# shower.net
KiCad netlist of a schematic drawn in Altium Designer
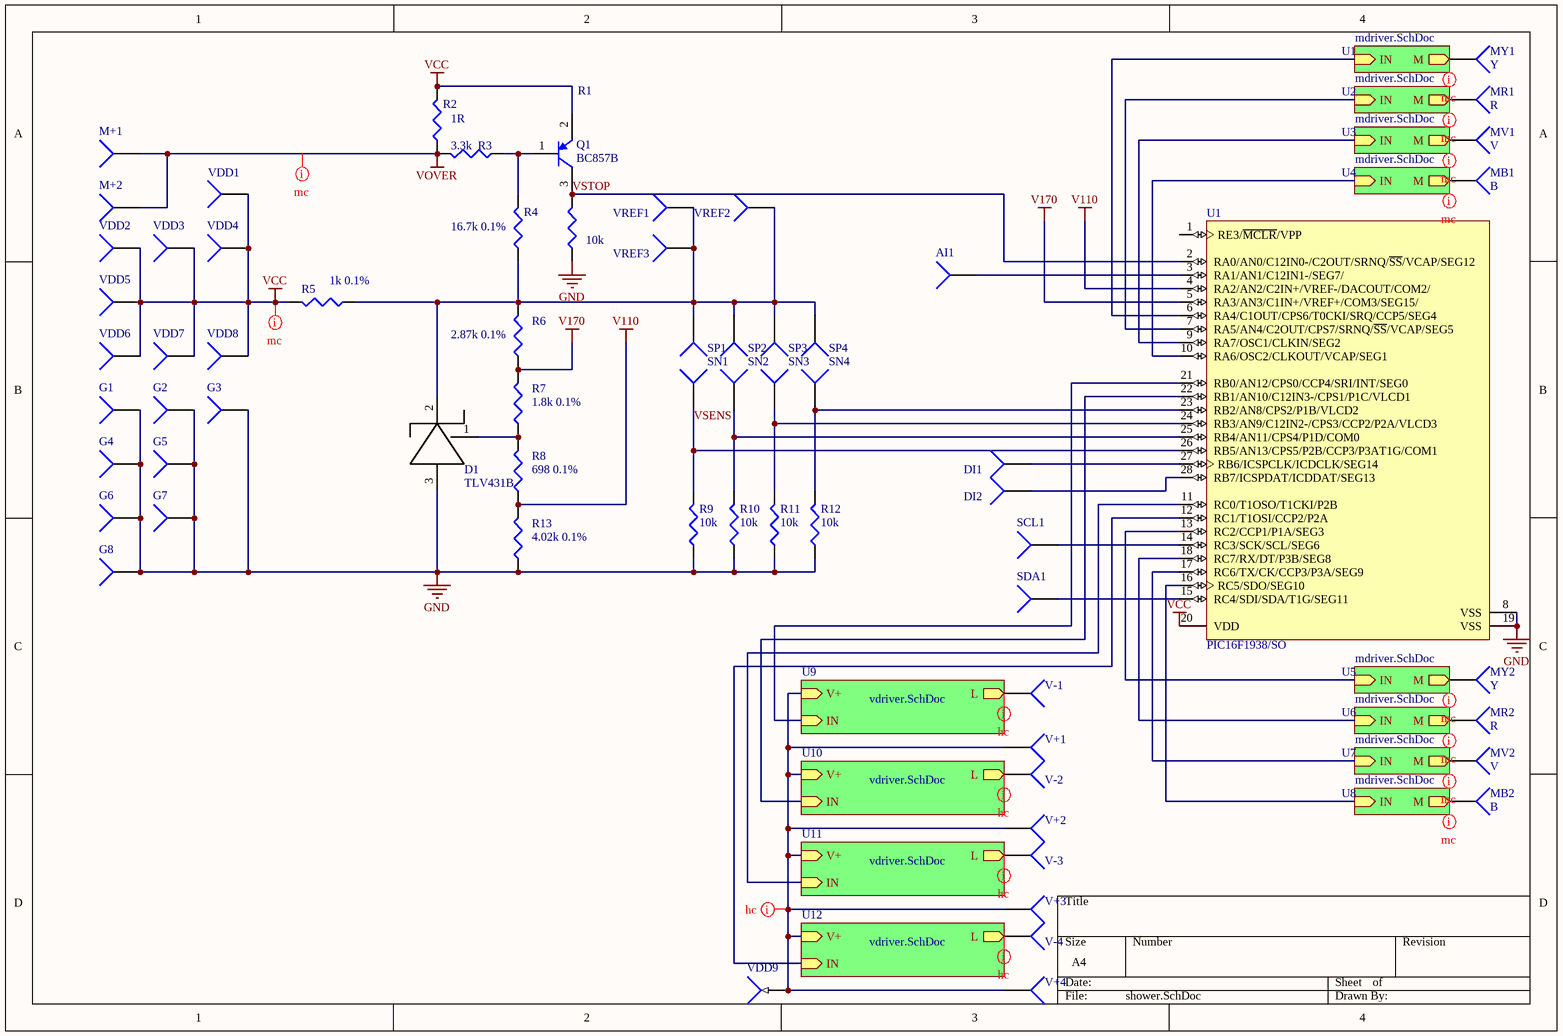
[diagram p0: shower.SchDoc]

(export (version "E")
  (design (tool "Eeschema 10.0.6"))
  (components
    (comp (ref "AI1")
      (value "+5V")
      (footprint "PIN1")
      (description "Socket")
      (fields (field (name "PUBLISHER") "Altium Limited"))
      (libsource (lib "misc") (part "Socket"))
    )
    (comp (ref "D1") (value "TLV431B") (footprint "SOT-23_N") (libsource (lib "misc") (part "TLV431A")))
    (comp (ref "DI1")
      (value "+5V")
      (footprint "PIN1")
      (description "Socket")
      (fields (field (name "PUBLISHER") "Altium Limited"))
      (libsource (lib "misc") (part "Socket"))
    )
    (comp (ref "DI2")
      (value "+5V")
      (footprint "PIN1")
      (description "Socket")
      (fields (field (name "PUBLISHER") "Altium Limited"))
      (libsource (lib "misc") (part "Socket"))
    )
    (comp (ref "G1")
      (value "Socket")
      (footprint "PIN1")
      (fields (field (name "PUBLISHER") "Altium Limited"))
      (libsource (lib "misc") (part "Socket"))
    )
    (comp (ref "G2")
      (value "Socket")
      (footprint "PIN1")
      (fields (field (name "PUBLISHER") "Altium Limited"))
      (libsource (lib "misc") (part "Socket"))
    )
    (comp (ref "G3")
      (value "Socket")
      (footprint "PIN1")
      (fields (field (name "PUBLISHER") "Altium Limited"))
      (libsource (lib "misc") (part "Socket"))
    )
    (comp (ref "G4")
      (value "Socket")
      (footprint "PIN1")
      (fields (field (name "PUBLISHER") "Altium Limited"))
      (libsource (lib "misc") (part "Socket"))
    )
    (comp (ref "G5")
      (value "Socket")
      (footprint "PIN1")
      (fields (field (name "PUBLISHER") "Altium Limited"))
      (libsource (lib "misc") (part "Socket"))
    )
    (comp (ref "G6")
      (value "Socket")
      (footprint "PIN1")
      (fields (field (name "PUBLISHER") "Altium Limited"))
      (libsource (lib "misc") (part "Socket"))
    )
    (comp (ref "G7")
      (value "Socket")
      (footprint "PIN1")
      (fields (field (name "PUBLISHER") "Altium Limited"))
      (libsource (lib "misc") (part "Socket"))
    )
    (comp (ref "G8")
      (value "Socket")
      (footprint "PIN1")
      (fields (field (name "PUBLISHER") "Altium Limited"))
      (libsource (lib "misc") (part "Socket"))
    )
    (comp (ref "M+1")
      (value "+5V")
      (footprint "PIN1")
      (description "Socket")
      (fields (field (name "PUBLISHER") "Altium Limited"))
      (libsource (lib "misc") (part "Socket"))
    )
    (comp (ref "M+2")
      (value "+5V")
      (footprint "PIN1")
      (description "Socket")
      (fields (field (name "PUBLISHER") "Altium Limited"))
      (libsource (lib "misc") (part "Socket"))
    )
    (comp (ref "MB1")
      (value "B")
      (footprint "PIN1")
      (description "Socket")
      (fields (field (name "PUBLISHER") "Altium Limited"))
      (libsource (lib "misc") (part "Socket"))
    )
    (comp (ref "MB2")
      (value "B")
      (footprint "PIN1")
      (description "Socket")
      (fields (field (name "PUBLISHER") "Altium Limited"))
      (libsource (lib "misc") (part "Socket"))
    )
    (comp (ref "MR1")
      (value "R")
      (footprint "PIN1")
      (description "Socket")
      (fields (field (name "PUBLISHER") "Altium Limited"))
      (libsource (lib "misc") (part "Socket"))
    )
    (comp (ref "MR2")
      (value "R")
      (footprint "PIN1")
      (description "Socket")
      (fields (field (name "PUBLISHER") "Altium Limited"))
      (libsource (lib "misc") (part "Socket"))
    )
    (comp (ref "MV1")
      (value "V")
      (footprint "PIN1")
      (description "Socket")
      (fields (field (name "PUBLISHER") "Altium Limited"))
      (libsource (lib "misc") (part "Socket"))
    )
    (comp (ref "MV2")
      (value "V")
      (footprint "PIN1")
      (description "Socket")
      (fields (field (name "PUBLISHER") "Altium Limited"))
      (libsource (lib "misc") (part "Socket"))
    )
    (comp (ref "MY1")
      (value "Y")
      (footprint "PIN1")
      (description "Socket")
      (fields (field (name "PUBLISHER") "Altium Limited"))
      (libsource (lib "misc") (part "Socket"))
    )
    (comp (ref "MY2")
      (value "Y")
      (footprint "PIN1")
      (description "Socket")
      (fields (field (name "PUBLISHER") "Altium Limited"))
      (libsource (lib "misc") (part "Socket"))
    )
    (comp (ref "Q1")
      (value "BC857B")
      (footprint "SOT-23_N")
      (description "PNP Bipolar Transistor")
      (fields (field (name "PUBLISHER") "Altium Limited"))
      (libsource (lib "Miscellaneous Devices") (part "PNP"))
    )
    (comp (ref "R1")
      (value "10k")
      (footprint "J1-0603")
      (description "Resistor")
      (fields (field (name "PUBLISHER") "Altium Limited"))
      (libsource (lib "Miscellaneous Devices") (part "Res3"))
    )
    (comp (ref "R2")
      (value "1R")
      (footprint "J1-0603")
      (description "Resistor")
      (fields (field (name "PUBLISHER") "Altium Limited"))
      (libsource (lib "Miscellaneous Devices") (part "Res3"))
    )
    (comp (ref "R3")
      (value "3.3k")
      (footprint "J1-0603")
      (description "Resistor")
      (fields (field (name "PUBLISHER") "Altium Limited"))
      (libsource (lib "Miscellaneous Devices") (part "Res3"))
    )
    (comp (ref "R4")
      (value "16.7k 0.1%")
      (footprint "J1-0603")
      (description "Resistor")
      (fields (field (name "PUBLISHER") "Altium Limited"))
      (libsource (lib "Miscellaneous Devices") (part "Res3"))
    )
    (comp (ref "R5")
      (value "1k 0.1%")
      (footprint "J1-0603")
      (description "Resistor")
      (fields (field (name "PUBLISHER") "Altium Limited"))
      (libsource (lib "Miscellaneous Devices") (part "Res3"))
    )
    (comp (ref "R6")
      (value "2.87k 0.1%")
      (footprint "J1-0603")
      (description "Resistor")
      (fields (field (name "PUBLISHER") "Altium Limited"))
      (libsource (lib "Miscellaneous Devices") (part "Res3"))
    )
    (comp (ref "R7")
      (value "1.8k 0.1%")
      (footprint "J1-0603")
      (description "Resistor")
      (fields (field (name "PUBLISHER") "Altium Limited"))
      (libsource (lib "Miscellaneous Devices") (part "Res3"))
    )
    (comp (ref "R8")
      (value "698 0.1%")
      (footprint "J1-0603")
      (description "Resistor")
      (fields (field (name "PUBLISHER") "Altium Limited"))
      (libsource (lib "Miscellaneous Devices") (part "Res3"))
    )
    (comp (ref "R9")
      (value "10k")
      (footprint "J1-0603")
      (description "Resistor")
      (fields (field (name "PUBLISHER") "Altium Limited"))
      (libsource (lib "Miscellaneous Devices") (part "Res3"))
    )
    (comp (ref "R10")
      (value "10k")
      (footprint "J1-0603")
      (description "Resistor")
      (fields (field (name "PUBLISHER") "Altium Limited"))
      (libsource (lib "Miscellaneous Devices") (part "Res3"))
    )
    (comp (ref "R11")
      (value "10k")
      (footprint "J1-0603")
      (description "Resistor")
      (fields (field (name "PUBLISHER") "Altium Limited"))
      (libsource (lib "Miscellaneous Devices") (part "Res3"))
    )
    (comp (ref "R12")
      (value "10k")
      (footprint "J1-0603")
      (description "Resistor")
      (fields (field (name "PUBLISHER") "Altium Limited"))
      (libsource (lib "Miscellaneous Devices") (part "Res3"))
    )
    (comp (ref "R13")
      (value "4.02k 0.1%")
      (footprint "J1-0603")
      (description "Resistor")
      (fields (field (name "PUBLISHER") "Altium Limited"))
      (libsource (lib "Miscellaneous Devices") (part "Res3"))
    )
    (comp (ref "SCL1")
      (value "+5V")
      (footprint "PIN1")
      (description "Socket")
      (fields (field (name "PUBLISHER") "Altium Limited"))
      (libsource (lib "misc") (part "Socket"))
    )
    (comp (ref "SDA1")
      (value "+5V")
      (footprint "PIN1")
      (description "Socket")
      (fields (field (name "PUBLISHER") "Altium Limited"))
      (libsource (lib "misc") (part "Socket"))
    )
    (comp (ref "SN1")
      (value "+5V")
      (footprint "PIN1")
      (description "Socket")
      (fields (field (name "PUBLISHER") "Altium Limited"))
      (libsource (lib "misc") (part "Socket"))
    )
    (comp (ref "SN2")
      (value "+5V")
      (footprint "PIN1")
      (description "Socket")
      (fields (field (name "PUBLISHER") "Altium Limited"))
      (libsource (lib "misc") (part "Socket"))
    )
    (comp (ref "SN3")
      (value "+5V")
      (footprint "PIN1")
      (description "Socket")
      (fields (field (name "PUBLISHER") "Altium Limited"))
      (libsource (lib "misc") (part "Socket"))
    )
    (comp (ref "SN4")
      (value "+5V")
      (footprint "PIN1")
      (description "Socket")
      (fields (field (name "PUBLISHER") "Altium Limited"))
      (libsource (lib "misc") (part "Socket"))
    )
    (comp (ref "SP1")
      (value "+5V")
      (footprint "PIN1")
      (description "Socket")
      (fields (field (name "PUBLISHER") "Altium Limited"))
      (libsource (lib "misc") (part "Socket"))
    )
    (comp (ref "SP2")
      (value "+5V")
      (footprint "PIN1")
      (description "Socket")
      (fields (field (name "PUBLISHER") "Altium Limited"))
      (libsource (lib "misc") (part "Socket"))
    )
    (comp (ref "SP3")
      (value "+5V")
      (footprint "PIN1")
      (description "Socket")
      (fields (field (name "PUBLISHER") "Altium Limited"))
      (libsource (lib "misc") (part "Socket"))
    )
    (comp (ref "SP4")
      (value "+5V")
      (footprint "PIN1")
      (description "Socket")
      (fields (field (name "PUBLISHER") "Altium Limited"))
      (libsource (lib "misc") (part "Socket"))
    )
    (comp (ref "U1")
      (value "PIC16F1938/SO")
      (footprint "SOIC-SO28_N")
      (fields (field (name "PUBLISHER") "Altium Limited"))
      (libsource (lib "Microchip Microcontroller 8-Bit PIC16") (part "PIC16F1936T-I/SO"))
    )
    (comp (ref "V+1")
      (value "+5V")
      (footprint "PIN1")
      (description "Socket")
      (fields (field (name "PUBLISHER") "Altium Limited"))
      (libsource (lib "misc") (part "Socket"))
    )
    (comp (ref "V+2")
      (value "+5V")
      (footprint "PIN1")
      (description "Socket")
      (fields (field (name "PUBLISHER") "Altium Limited"))
      (libsource (lib "misc") (part "Socket"))
    )
    (comp (ref "V+3")
      (value "+5V")
      (footprint "PIN1")
      (description "Socket")
      (fields (field (name "PUBLISHER") "Altium Limited"))
      (libsource (lib "misc") (part "Socket"))
    )
    (comp (ref "V+4")
      (value "+5V")
      (footprint "PIN1")
      (description "Socket")
      (fields (field (name "PUBLISHER") "Altium Limited"))
      (libsource (lib "misc") (part "Socket"))
    )
    (comp (ref "V-1")
      (value "+5V")
      (footprint "PIN1")
      (description "Socket")
      (fields (field (name "PUBLISHER") "Altium Limited"))
      (libsource (lib "misc") (part "Socket"))
    )
    (comp (ref "V-2")
      (value "+5V")
      (footprint "PIN1")
      (description "Socket")
      (fields (field (name "PUBLISHER") "Altium Limited"))
      (libsource (lib "misc") (part "Socket"))
    )
    (comp (ref "V-3")
      (value "+5V")
      (footprint "PIN1")
      (description "Socket")
      (fields (field (name "PUBLISHER") "Altium Limited"))
      (libsource (lib "misc") (part "Socket"))
    )
    (comp (ref "V-4")
      (value "+5V")
      (footprint "PIN1")
      (description "Socket")
      (fields (field (name "PUBLISHER") "Altium Limited"))
      (libsource (lib "misc") (part "Socket"))
    )
    (comp (ref "VDD1")
      (value "+5V")
      (footprint "PIN1")
      (description "Socket")
      (fields (field (name "PUBLISHER") "Altium Limited"))
      (libsource (lib "misc") (part "Socket"))
    )
    (comp (ref "VDD2")
      (value "+5V")
      (footprint "PIN1")
      (description "Socket")
      (fields (field (name "PUBLISHER") "Altium Limited"))
      (libsource (lib "misc") (part "Socket"))
    )
    (comp (ref "VDD3")
      (value "+5V")
      (footprint "PIN1")
      (description "Socket")
      (fields (field (name "PUBLISHER") "Altium Limited"))
      (libsource (lib "misc") (part "Socket"))
    )
    (comp (ref "VDD4")
      (value "+5V")
      (footprint "PIN1")
      (description "Socket")
      (fields (field (name "PUBLISHER") "Altium Limited"))
      (libsource (lib "misc") (part "Socket"))
    )
    (comp (ref "VDD5")
      (value "+5V")
      (footprint "PIN1")
      (description "Socket")
      (fields (field (name "PUBLISHER") "Altium Limited"))
      (libsource (lib "misc") (part "Socket"))
    )
    (comp (ref "VDD6")
      (value "+5V")
      (footprint "PIN1")
      (description "Socket")
      (fields (field (name "PUBLISHER") "Altium Limited"))
      (libsource (lib "misc") (part "Socket"))
    )
    (comp (ref "VDD7")
      (value "+5V")
      (footprint "PIN1")
      (description "Socket")
      (fields (field (name "PUBLISHER") "Altium Limited"))
      (libsource (lib "misc") (part "Socket"))
    )
    (comp (ref "VDD8")
      (value "+5V")
      (footprint "PIN1")
      (description "Socket")
      (fields (field (name "PUBLISHER") "Altium Limited"))
      (libsource (lib "misc") (part "Socket"))
    )
    (comp (ref "VDD9")
      (value "+5V")
      (footprint "PIN1")
      (description "Socket")
      (fields (field (name "PUBLISHER") "Altium Limited"))
      (libsource (lib "misc") (part "Socket"))
    )
    (comp (ref "VREF1")
      (value "+5V")
      (footprint "PIN1")
      (description "Socket")
      (fields (field (name "PUBLISHER") "Altium Limited"))
      (libsource (lib "misc") (part "Socket"))
    )
    (comp (ref "VREF2")
      (value "+5V")
      (footprint "PIN1")
      (description "Socket")
      (fields (field (name "PUBLISHER") "Altium Limited"))
      (libsource (lib "misc") (part "Socket"))
    )
    (comp (ref "VREF3")
      (value "+5V")
      (footprint "PIN1")
      (description "Socket")
      (fields (field (name "PUBLISHER") "Altium Limited"))
      (libsource (lib "misc") (part "Socket"))
    )
  )
  (nets
    (net (code "1") (name "/IN") (class "Default")
      (node (ref "U1") (pin "18") (pinfunction "RC7/RX/DT/P3B/SEG8_18") (pintype "bidirectional"))
    )
    (net (code "2") (name "/IN_1") (class "Default")
      (node (ref "U1") (pin "12") (pinfunction "RC1/T1OSI/CCP2/P2A_12") (pintype "bidirectional"))
    )
    (net (code "3") (name "/IN_2") (class "Default")
      (node (ref "U1") (pin "11") (pinfunction "RC0/T1OSO/T1CKI/P2B_11") (pintype "bidirectional"))
    )
    (net (code "4") (name "/IN_3") (class "Default")
      (node (ref "U1") (pin "22") (pinfunction "RB1/AN10/C12IN3-/CPS1/P1C/VLCD1_22") (pintype "bidirectional"))
    )
    (net (code "5") (name "/IN_4") (class "Default")
      (node (ref "U1") (pin "21") (pinfunction "RB0/AN12/CPS0/CCP4/SRI/INT/SEG0_21") (pintype "bidirectional"))
    )
    (net (code "6") (name "/IN_5") (class "Default")
      (node (ref "U1") (pin "13") (pinfunction "RC2/CCP1/P1A/SEG3_13") (pintype "bidirectional"))
    )
    (net (code "7") (name "/IN_6") (class "Default")
      (node (ref "U1") (pin "17") (pinfunction "RC6/TX/CK/CCP3/P3A/SEG9_17") (pintype "bidirectional"))
    )
    (net (code "8") (name "/IN_7") (class "Default")
      (node (ref "U1") (pin "16") (pinfunction "RC5/SDO/SEG10_16") (pintype "bidirectional"))
    )
    (net (code "9") (name "/IN_8") (class "Default")
      (node (ref "U1") (pin "6") (pinfunction "RA4/C1OUT/CPS6/T0CKI/SRQ/CCP5/SEG4_6") (pintype "bidirectional"))
    )
    (net (code "10") (name "/IN_9") (class "Default")
      (node (ref "U1") (pin "7") (pinfunction "RA5/AN4/C2OUT/CPS7/SRNQ/~{SS}/VCAP/SEG5_7") (pintype "bidirectional"))
    )
    (net (code "11") (name "/IN_10") (class "Default")
      (node (ref "U1") (pin "9") (pinfunction "RA7/OSC1/CLKIN/SEG2_9") (pintype "bidirectional"))
    )
    (net (code "12") (name "/IN_11") (class "Default")
      (node (ref "U1") (pin "10") (pinfunction "RA6/OSC2/CLKOUT/VCAP/SEG1_10") (pintype "bidirectional"))
    )
    (net (code "13") (name "/L") (class "Default")
      (node (ref "V-4") (pin "1") (pinfunction "1_1") (pintype "passive"))
    )
    (net (code "14") (name "/L_1") (class "Default")
      (node (ref "V-3") (pin "1") (pinfunction "1_1") (pintype "passive"))
    )
    (net (code "15") (name "/L_2") (class "Default")
      (node (ref "V-1") (pin "1") (pinfunction "1_1") (pintype "passive"))
    )
    (net (code "16") (name "/L_3") (class "Default")
      (node (ref "V-2") (pin "1") (pinfunction "1_1") (pintype "passive"))
    )
    (net (code "17") (name "/M") (class "Default")
      (node (ref "MB2") (pin "1") (pinfunction "1_1") (pintype "passive"))
    )
    (net (code "18") (name "/M_1") (class "Default")
      (node (ref "MB1") (pin "1") (pinfunction "1_1") (pintype "passive"))
    )
    (net (code "19") (name "/M_2") (class "Default")
      (node (ref "MR1") (pin "1") (pinfunction "1_1") (pintype "passive"))
    )
    (net (code "20") (name "/M_3") (class "Default")
      (node (ref "MV1") (pin "1") (pinfunction "1_1") (pintype "passive"))
    )
    (net (code "21") (name "/M_4") (class "Default")
      (node (ref "MY1") (pin "1") (pinfunction "1_1") (pintype "passive"))
    )
    (net (code "22") (name "/M_5") (class "Default")
      (node (ref "MY2") (pin "1") (pinfunction "1_1") (pintype "passive"))
    )
    (net (code "23") (name "/M_6") (class "Default")
      (node (ref "MR2") (pin "1") (pinfunction "1_1") (pintype "passive"))
    )
    (net (code "24") (name "/M_7") (class "Default")
      (node (ref "MV2") (pin "1") (pinfunction "1_1") (pintype "passive"))
    )
    (net (code "25") (name "/V+") (class "Default")
      (node (ref "V+1") (pin "1") (pinfunction "1_1") (pintype "passive"))
      (node (ref "V+2") (pin "1") (pinfunction "1_1") (pintype "passive"))
      (node (ref "V+3") (pin "1") (pinfunction "1_1") (pintype "passive"))
      (node (ref "V+4") (pin "1") (pinfunction "1_1") (pintype "passive"))
      (node (ref "VDD9") (pin "1") (pinfunction "1_1") (pintype "passive"))
    )
    (net (code "26") (name "/VSENS") (class "Default")
      (node (ref "R9") (pin "2") (pinfunction "2_2") (pintype "passive"))
      (node (ref "SN1") (pin "1") (pinfunction "1_1") (pintype "passive"))
      (node (ref "U1") (pin "26") (pinfunction "RB5/AN13/CPS5/P2B/CCP3/P3AT1G/COM1_26") (pintype "bidirectional"))
    )
    (net (code "27") (name "/VSTOP") (class "Default")
      (node (ref "Q1") (pin "3") (pinfunction "C_3") (pintype "passive"))
      (node (ref "R1") (pin "2") (pinfunction "2_2") (pintype "passive"))
      (node (ref "U1") (pin "2") (pinfunction "RA0/AN0/C12IN0-/C2OUT/SRNQ/~{SS}/VCAP/SEG12_2") (pintype "bidirectional"))
    )
    (net (code "28") (name "GND") (class "Default")
      (node (ref "D1") (pin "3") (pinfunction "3_3") (pintype "passive"))
      (node (ref "G1") (pin "1") (pinfunction "1_1") (pintype "passive"))
      (node (ref "G2") (pin "1") (pinfunction "1_1") (pintype "passive"))
      (node (ref "G3") (pin "1") (pinfunction "1_1") (pintype "passive"))
      (node (ref "G4") (pin "1") (pinfunction "1_1") (pintype "passive"))
      (node (ref "G5") (pin "1") (pinfunction "1_1") (pintype "passive"))
      (node (ref "G6") (pin "1") (pinfunction "1_1") (pintype "passive"))
      (node (ref "G7") (pin "1") (pinfunction "1_1") (pintype "passive"))
      (node (ref "G8") (pin "1") (pinfunction "1_1") (pintype "passive"))
      (node (ref "R1") (pin "1") (pinfunction "1_1") (pintype "passive"))
      (node (ref "R10") (pin "1") (pinfunction "1_1") (pintype "passive"))
      (node (ref "R11") (pin "1") (pinfunction "1_1") (pintype "passive"))
      (node (ref "R12") (pin "1") (pinfunction "1_1") (pintype "passive"))
      (node (ref "R13") (pin "1") (pinfunction "1_1") (pintype "passive"))
      (node (ref "R9") (pin "1") (pinfunction "1_1") (pintype "passive"))
      (node (ref "U1") (pin "19") (pinfunction "VSS_19") (pintype "power_in"))
      (node (ref "U1") (pin "8") (pinfunction "VSS_8") (pintype "power_in"))
    )
    (net (code "29") (name "Net-(D1-Pad1)") (class "Default")
      (node (ref "D1") (pin "1") (pinfunction "1_1") (pintype "passive"))
      (node (ref "R7") (pin "1") (pinfunction "1_1") (pintype "passive"))
      (node (ref "R8") (pin "2") (pinfunction "2_2") (pintype "passive"))
    )
    (net (code "30") (name "Net-(D1-Pad2)") (class "Default")
      (node (ref "D1") (pin "2") (pinfunction "2_2") (pintype "passive"))
      (node (ref "R4") (pin "1") (pinfunction "1_1") (pintype "passive"))
      (node (ref "R5") (pin "1") (pinfunction "1_1") (pintype "passive"))
      (node (ref "R6") (pin "2") (pinfunction "2_2") (pintype "passive"))
      (node (ref "SP1") (pin "1") (pinfunction "1_1") (pintype "passive"))
      (node (ref "SP2") (pin "1") (pinfunction "1_1") (pintype "passive"))
      (node (ref "SP3") (pin "1") (pinfunction "1_1") (pintype "passive"))
      (node (ref "SP4") (pin "1") (pinfunction "1_1") (pintype "passive"))
      (node (ref "VREF1") (pin "1") (pinfunction "1_1") (pintype "passive"))
      (node (ref "VREF2") (pin "1") (pinfunction "1_1") (pintype "passive"))
      (node (ref "VREF3") (pin "1") (pinfunction "1_1") (pintype "passive"))
    )
    (net (code "31") (name "Net-(Q1-B)") (class "Default")
      (node (ref "Q1") (pin "1") (pinfunction "B_1") (pintype "passive"))
      (node (ref "R3") (pin "1") (pinfunction "1_1") (pintype "passive"))
      (node (ref "R4") (pin "2") (pinfunction "2_2") (pintype "passive"))
    )
    (net (code "32") (name "Net-(U1-RA1{slash}AN1{slash}C12IN1-{slash}SEG7{slash})") (class "Default")
      (node (ref "AI1") (pin "1") (pinfunction "1_1") (pintype "passive"))
      (node (ref "U1") (pin "3") (pinfunction "RA1/AN1/C12IN1-/SEG7/_3") (pintype "bidirectional"))
    )
    (net (code "33") (name "Net-(U1-RB2{slash}AN8{slash}CPS2{slash}P1B{slash}VLCD2)") (class "Default")
      (node (ref "R12") (pin "2") (pinfunction "2_2") (pintype "passive"))
      (node (ref "SN4") (pin "1") (pinfunction "1_1") (pintype "passive"))
      (node (ref "U1") (pin "23") (pinfunction "RB2/AN8/CPS2/P1B/VLCD2_23") (pintype "bidirectional"))
    )
    (net (code "34") (name "Net-(U1-RB3{slash}AN9{slash}C12IN2-{slash}CPS3{slash}CCP2{slash}P2A{slash}VLCD3)") (class "Default")
      (node (ref "R11") (pin "2") (pinfunction "2_2") (pintype "passive"))
      (node (ref "SN3") (pin "1") (pinfunction "1_1") (pintype "passive"))
      (node (ref "U1") (pin "24") (pinfunction "RB3/AN9/C12IN2-/CPS3/CCP2/P2A/VLCD3_24") (pintype "bidirectional"))
    )
    (net (code "35") (name "Net-(U1-RB4{slash}AN11{slash}CPS4{slash}P1D{slash}COM0)") (class "Default")
      (node (ref "R10") (pin "2") (pinfunction "2_2") (pintype "passive"))
      (node (ref "SN2") (pin "1") (pinfunction "1_1") (pintype "passive"))
      (node (ref "U1") (pin "25") (pinfunction "RB4/AN11/CPS4/P1D/COM0_25") (pintype "bidirectional"))
    )
    (net (code "36") (name "Net-(U1-RB6{slash}ICSPCLK{slash}ICDCLK{slash}SEG14)") (class "Default")
      (node (ref "DI1") (pin "1") (pinfunction "1_1") (pintype "passive"))
      (node (ref "U1") (pin "27") (pinfunction "RB6/ICSPCLK/ICDCLK/SEG14_27") (pintype "bidirectional"))
    )
    (net (code "37") (name "Net-(U1-RB7{slash}ICSPDAT{slash}ICDDAT{slash}SEG13)") (class "Default")
      (node (ref "DI2") (pin "1") (pinfunction "1_1") (pintype "passive"))
      (node (ref "U1") (pin "28") (pinfunction "RB7/ICSPDAT/ICDDAT/SEG13_28") (pintype "bidirectional"))
    )
    (net (code "38") (name "Net-(U1-RC3{slash}SCK{slash}SCL{slash}SEG6)") (class "Default")
      (node (ref "SCL1") (pin "1") (pinfunction "1_1") (pintype "passive"))
      (node (ref "U1") (pin "14") (pinfunction "RC3/SCK/SCL/SEG6_14") (pintype "bidirectional"))
    )
    (net (code "39") (name "Net-(U1-RC4{slash}SDI{slash}SDA{slash}T1G{slash}SEG11)") (class "Default")
      (node (ref "SDA1") (pin "1") (pinfunction "1_1") (pintype "passive"))
      (node (ref "U1") (pin "15") (pinfunction "RC4/SDI/SDA/T1G/SEG11_15") (pintype "bidirectional"))
    )
    (net (code "40") (name "V110") (class "Default")
      (node (ref "R13") (pin "2") (pinfunction "2_2") (pintype "passive"))
      (node (ref "R8") (pin "1") (pinfunction "1_1") (pintype "passive"))
      (node (ref "U1") (pin "4") (pinfunction "RA2/AN2/C2IN+/VREF-/DACOUT/COM2/_4") (pintype "bidirectional"))
    )
    (net (code "41") (name "V170") (class "Default")
      (node (ref "R6") (pin "1") (pinfunction "1_1") (pintype "passive"))
      (node (ref "R7") (pin "2") (pinfunction "2_2") (pintype "passive"))
      (node (ref "U1") (pin "5") (pinfunction "RA3/AN3/C1IN+/VREF+/COM3/SEG15/_5") (pintype "bidirectional"))
    )
    (net (code "42") (name "VCC") (class "Default")
      (node (ref "Q1") (pin "2") (pinfunction "E_2") (pintype "passive"))
      (node (ref "R2") (pin "2") (pinfunction "2_2") (pintype "passive"))
      (node (ref "R5") (pin "2") (pinfunction "2_2") (pintype "passive"))
      (node (ref "U1") (pin "20") (pinfunction "VDD_20") (pintype "power_in"))
      (node (ref "VDD1") (pin "1") (pinfunction "1_1") (pintype "passive"))
      (node (ref "VDD2") (pin "1") (pinfunction "1_1") (pintype "passive"))
      (node (ref "VDD3") (pin "1") (pinfunction "1_1") (pintype "passive"))
      (node (ref "VDD4") (pin "1") (pinfunction "1_1") (pintype "passive"))
      (node (ref "VDD5") (pin "1") (pinfunction "1_1") (pintype "passive"))
      (node (ref "VDD6") (pin "1") (pinfunction "1_1") (pintype "passive"))
      (node (ref "VDD7") (pin "1") (pinfunction "1_1") (pintype "passive"))
      (node (ref "VDD8") (pin "1") (pinfunction "1_1") (pintype "passive"))
    )
    (net (code "43") (name "VOVER") (class "Default")
      (node (ref "M+1") (pin "1") (pinfunction "1_1") (pintype "passive"))
      (node (ref "M+2") (pin "1") (pinfunction "1_1") (pintype "passive"))
      (node (ref "R2") (pin "1") (pinfunction "1_1") (pintype "passive"))
      (node (ref "R3") (pin "2") (pinfunction "2_2") (pintype "passive"))
    )
    (net (code "44") (name "unconnected-(U1-RE3{slash}~{MCLR}{slash}VPP-Pad1)") (class "Default")
      (node (ref "U1") (pin "1") (pinfunction "RE3/~{MCLR}/VPP_1") (pintype "bidirectional"))
    )
  )
)
